# pressureMv4.net
KiCad netlist of a schematic drawn in EAGLE
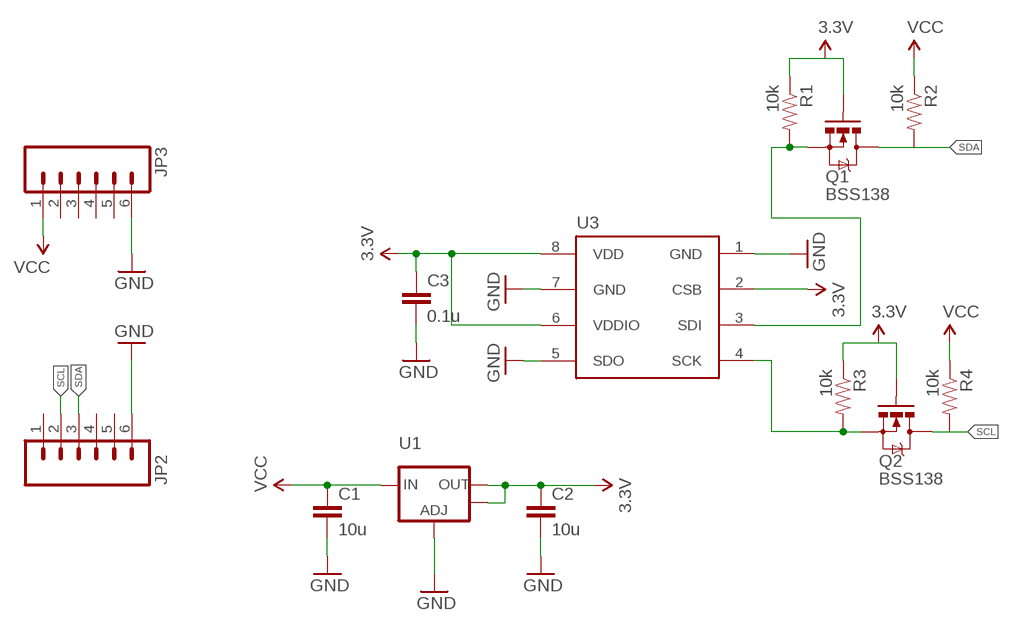
[diagram p0: schematic, sheet 1]

(export (version "E")
  (design (tool "Eeschema 10.0.6"))
  (components
    (comp (ref "C1")
      (value "10u")
      (footprint "eagle-import:0805")
      (libsource (lib "eagle-import") (part "CAP0805"))
    )
    (comp (ref "C2")
      (value "10u")
      (footprint "eagle-import:0805")
      (libsource (lib "eagle-import") (part "CAP0805"))
    )
    (comp (ref "C3")
      (value "0.1u")
      (footprint "eagle-import:0805")
      (libsource (lib "eagle-import") (part "CAP0805"))
    )
    (comp (ref "JP2")
      (value "M06LOCK_LONGPADS")
      (footprint "eagle-import:1X06_LOCK_LONGPADS")
      (libsource (lib "eagle-import") (part "M06LOCK_LONGPADS"))
    )
    (comp (ref "JP3")
      (value "M06LOCK_LONGPADS")
      (footprint "eagle-import:1X06_LOCK_LONGPADS")
      (libsource (lib "eagle-import") (part "M06LOCK_LONGPADS"))
    )
    (comp (ref "Q1")
      (value "BSS138")
      (footprint "eagle-import:SOT323")
      (libsource (lib "eagle-import") (part "MOSFET-NCHANNEL2N7002PW"))
    )
    (comp (ref "Q2")
      (value "BSS138")
      (footprint "eagle-import:SOT323")
      (libsource (lib "eagle-import") (part "MOSFET-NCHANNEL2N7002PW"))
    )
    (comp (ref "R1")
      (value "10k")
      (footprint "eagle-import:0805")
      (libsource (lib "eagle-import") (part "RESISTOR0805-RES"))
    )
    (comp (ref "R2")
      (value "10k")
      (footprint "eagle-import:0805")
      (libsource (lib "eagle-import") (part "RESISTOR0805-RES"))
    )
    (comp (ref "R3")
      (value "10k")
      (footprint "eagle-import:0805")
      (libsource (lib "eagle-import") (part "RESISTOR0805-RES"))
    )
    (comp (ref "R4")
      (value "10k")
      (footprint "eagle-import:0805")
      (libsource (lib "eagle-import") (part "RESISTOR0805-RES"))
    )
    (comp (ref "U1")
      (value "V_REG_LM1117SOT223")
      (footprint "eagle-import:SOT223")
      (libsource (lib "eagle-import") (part "V_REG_LM1117SOT223"))
    )
    (comp (ref "U3")
      (value "BME280SMD")
      (footprint "eagle-import:BME280")
      (libsource (lib "eagle-import") (part "BME280SMD"))
    )
  )
  (nets
    (net (code "1") (name "3.3V") (class "Default")
      (node (ref "C2") (pin "1") (pinfunction "1_1") (pintype "passive"))
      (node (ref "C3") (pin "1") (pinfunction "1_1") (pintype "passive"))
      (node (ref "Q1") (pin "1") (pinfunction "G_1") (pintype "passive"))
      (node (ref "Q2") (pin "1") (pinfunction "G_1") (pintype "passive"))
      (node (ref "R1") (pin "1") (pinfunction "1_1") (pintype "passive"))
      (node (ref "R3") (pin "1") (pinfunction "1_1") (pintype "passive"))
      (node (ref "U1") (pin "2") (pinfunction "OUT_2") (pintype "output"))
      (node (ref "U1") (pin "4") (pinfunction "OUT_4") (pintype "output"))
      (node (ref "U3") (pin "2") (pinfunction "CSB_2") (pintype "bidirectional"))
      (node (ref "U3") (pin "6") (pinfunction "VDDIO_6") (pintype "bidirectional"))
      (node (ref "U3") (pin "8") (pinfunction "VDD_8") (pintype "power_in"))
    )
    (net (code "2") (name "GND") (class "Default")
      (node (ref "C1") (pin "2") (pinfunction "2_2") (pintype "passive"))
      (node (ref "C2") (pin "2") (pinfunction "2_2") (pintype "passive"))
      (node (ref "C3") (pin "2") (pinfunction "2_2") (pintype "passive"))
      (node (ref "JP2") (pin "6") (pinfunction "6_6") (pintype "passive"))
      (node (ref "JP3") (pin "6") (pinfunction "6_6") (pintype "passive"))
      (node (ref "U1") (pin "1") (pinfunction "ADJ_1") (pintype "input"))
      (node (ref "U3") (pin "1") (pinfunction "GND_1") (pintype "power_in"))
      (node (ref "U3") (pin "5") (pinfunction "SDO_5") (pintype "bidirectional"))
      (node (ref "U3") (pin "7") (pinfunction "GND_7") (pintype "power_in"))
    )
    (net (code "3") (name "Net-(Q1-S)") (class "Default")
      (node (ref "Q1") (pin "2") (pinfunction "S_2") (pintype "passive"))
      (node (ref "R1") (pin "2") (pinfunction "2_2") (pintype "passive"))
      (node (ref "U3") (pin "3") (pinfunction "SDI_3") (pintype "bidirectional"))
    )
    (net (code "4") (name "Net-(Q2-S)") (class "Default")
      (node (ref "Q2") (pin "2") (pinfunction "S_2") (pintype "passive"))
      (node (ref "R3") (pin "2") (pinfunction "2_2") (pintype "passive"))
      (node (ref "U3") (pin "4") (pinfunction "SCK_4") (pintype "bidirectional"))
    )
    (net (code "5") (name "SCL") (class "Default")
      (node (ref "JP2") (pin "2") (pinfunction "2_2") (pintype "passive"))
      (node (ref "Q2") (pin "3") (pinfunction "D_3") (pintype "passive"))
      (node (ref "R4") (pin "2") (pinfunction "2_2") (pintype "passive"))
    )
    (net (code "6") (name "SDA") (class "Default")
      (node (ref "JP2") (pin "3") (pinfunction "3_3") (pintype "passive"))
      (node (ref "Q1") (pin "3") (pinfunction "D_3") (pintype "passive"))
      (node (ref "R2") (pin "2") (pinfunction "2_2") (pintype "passive"))
    )
    (net (code "7") (name "VCC") (class "Default")
      (node (ref "C1") (pin "1") (pinfunction "1_1") (pintype "passive"))
      (node (ref "JP3") (pin "1") (pinfunction "1_1") (pintype "passive"))
      (node (ref "R2") (pin "1") (pinfunction "1_1") (pintype "passive"))
      (node (ref "R4") (pin "1") (pinfunction "1_1") (pintype "passive"))
      (node (ref "U1") (pin "3") (pinfunction "IN_3") (pintype "input"))
    )
    (net (code "8") (name "unconnected-(JP2-Pad1)") (class "Default")
      (node (ref "JP2") (pin "1") (pinfunction "1_1") (pintype "passive"))
    )
    (net (code "9") (name "unconnected-(JP2-Pad4)") (class "Default")
      (node (ref "JP2") (pin "4") (pinfunction "4_4") (pintype "passive"))
    )
    (net (code "10") (name "unconnected-(JP2-Pad5)") (class "Default")
      (node (ref "JP2") (pin "5") (pinfunction "5_5") (pintype "passive"))
    )
    (net (code "11") (name "unconnected-(JP3-Pad2)") (class "Default")
      (node (ref "JP3") (pin "2") (pinfunction "2_2") (pintype "passive"))
    )
    (net (code "12") (name "unconnected-(JP3-Pad3)") (class "Default")
      (node (ref "JP3") (pin "3") (pinfunction "3_3") (pintype "passive"))
    )
    (net (code "13") (name "unconnected-(JP3-Pad4)") (class "Default")
      (node (ref "JP3") (pin "4") (pinfunction "4_4") (pintype "passive"))
    )
    (net (code "14") (name "unconnected-(JP3-Pad5)") (class "Default")
      (node (ref "JP3") (pin "5") (pinfunction "5_5") (pintype "passive"))
    )
  )
)
